# Feuille1.net
KiCad netlist of a schematic drawn in Altium Designer
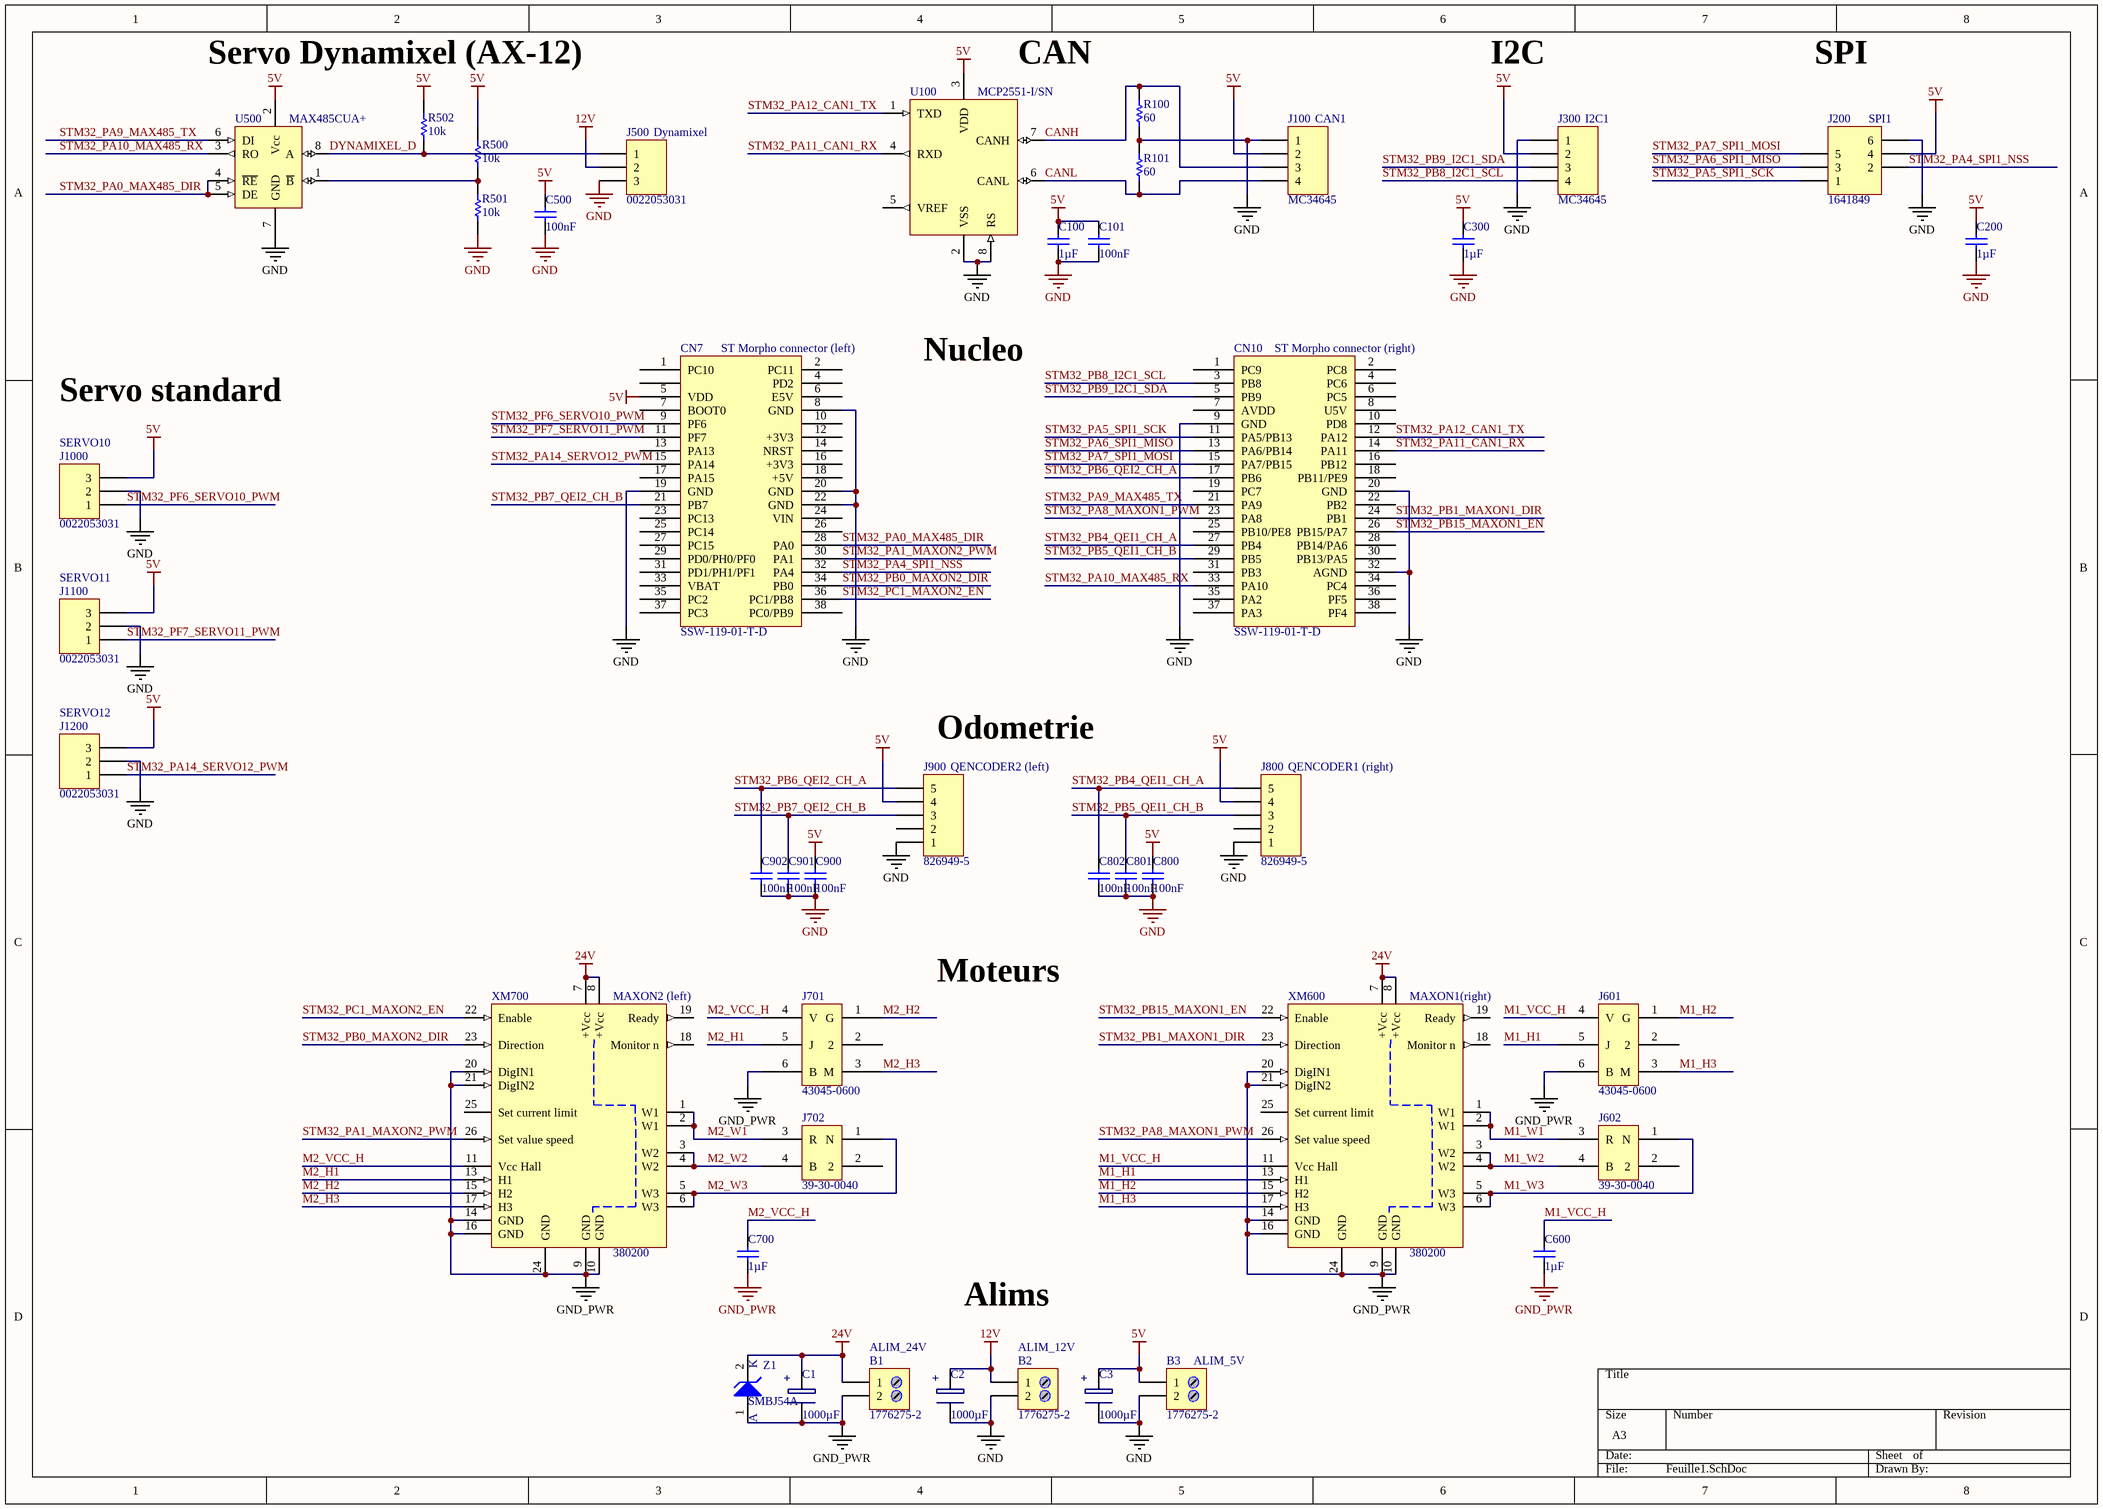
[diagram p0: Feuille1.SchDoc]

(export (version "E")
  (design (tool "Eeschema 10.0.6"))
  (components
    (comp (ref "B1")
      (value "1776275-2")
      (footprint "BORNIER_2V_3.5MM")
      (description "TERM BLOCK 2POS SIDE ENT 3.5MM")
      (fields (field (name "MANUFACTURER") "TE Connectivity AMP Connectors"))
      (libsource (lib "Divers") (part "1776275-2"))
    )
    (comp (ref "B2")
      (value "1776275-2")
      (footprint "BORNIER_2V_3.5MM")
      (description "TERM BLOCK 2POS SIDE ENT 3.5MM")
      (fields (field (name "MANUFACTURER") "TE Connectivity AMP Connectors"))
      (libsource (lib "Divers") (part "1776275-2"))
    )
    (comp (ref "B3")
      (value "1776275-2")
      (footprint "BORNIER_2V_3.5MM")
      (description "TERM BLOCK 2POS SIDE ENT 3.5MM")
      (fields (field (name "MANUFACTURER") "TE Connectivity AMP Connectors"))
      (libsource (lib "Divers") (part "1776275-2"))
    )
    (comp (ref "C1")
      (value "1000µF")
      (footprint "C_10mm")
      (fields
        (field (name "MANUFACTURER") "PANASONIC")
        (field (name "MANUFACTURER PART NUMBER") "EEUHD1E102")
      )
      (libsource (lib "Capas_Chimiques") (part "C_1000µF"))
    )
    (comp (ref "C2")
      (value "1000µF")
      (footprint "C_10mm")
      (fields
        (field (name "MANUFACTURER") "PANASONIC")
        (field (name "MANUFACTURER PART NUMBER") "EEUHD1E102")
      )
      (libsource (lib "Capas_Chimiques") (part "C_1000µF"))
    )
    (comp (ref "C3")
      (value "1000µF")
      (footprint "C_10mm")
      (fields
        (field (name "MANUFACTURER") "PANASONIC")
        (field (name "MANUFACTURER PART NUMBER") "EEUHD1E102")
      )
      (libsource (lib "Capas_Chimiques") (part "C_1000µF"))
    )
    (comp (ref "C100")
      (value "1µF")
      (footprint "C0805_N")
      (description "Capacitor")
      (fields (field (name "PUBLISHER") "Altium Limited"))
      (libsource (lib "_ROBOT") (part "Condensateur"))
    )
    (comp (ref "C101")
      (value "100nF")
      (footprint "C0805_N")
      (description "Capacitor")
      (fields (field (name "PUBLISHER") "Altium Limited"))
      (libsource (lib "_ROBOT") (part "Condensateur"))
    )
    (comp (ref "C200")
      (value "1µF")
      (footprint "C0805_N")
      (description "Capacitor")
      (fields (field (name "PUBLISHER") "Altium Limited"))
      (libsource (lib "_ROBOT") (part "Condensateur"))
    )
    (comp (ref "C300")
      (value "1µF")
      (footprint "C0805_N")
      (description "Capacitor")
      (fields (field (name "PUBLISHER") "Altium Limited"))
      (libsource (lib "_ROBOT") (part "Condensateur"))
    )
    (comp (ref "C500")
      (value "100nF")
      (footprint "C0805_N")
      (description "Capacitor")
      (fields (field (name "PUBLISHER") "Altium Limited"))
      (libsource (lib "_ROBOT") (part "Condensateur"))
    )
    (comp (ref "C600")
      (value "1µF")
      (footprint "C0805_N")
      (description "Capacitor")
      (fields (field (name "PUBLISHER") "Altium Limited"))
      (libsource (lib "_ROBOT") (part "Condensateur"))
    )
    (comp (ref "C700")
      (value "1µF")
      (footprint "C0805_N")
      (description "Capacitor")
      (fields (field (name "PUBLISHER") "Altium Limited"))
      (libsource (lib "_ROBOT") (part "Condensateur"))
    )
    (comp (ref "C800")
      (value "100nF")
      (footprint "C0805_N")
      (description "Capacitor")
      (fields (field (name "PUBLISHER") "Altium Limited"))
      (libsource (lib "_ROBOT") (part "Condensateur"))
    )
    (comp (ref "C801")
      (value "100nF")
      (footprint "C0805_N")
      (description "Capacitor")
      (fields (field (name "PUBLISHER") "Altium Limited"))
      (libsource (lib "_ROBOT") (part "Condensateur"))
    )
    (comp (ref "C802")
      (value "100nF")
      (footprint "C0805_N")
      (description "Capacitor")
      (fields (field (name "PUBLISHER") "Altium Limited"))
      (libsource (lib "_ROBOT") (part "Condensateur"))
    )
    (comp (ref "C900")
      (value "100nF")
      (footprint "C0805_N")
      (description "Capacitor")
      (fields (field (name "PUBLISHER") "Altium Limited"))
      (libsource (lib "_ROBOT") (part "Condensateur"))
    )
    (comp (ref "C901")
      (value "100nF")
      (footprint "C0805_N")
      (description "Capacitor")
      (fields (field (name "PUBLISHER") "Altium Limited"))
      (libsource (lib "_ROBOT") (part "Condensateur"))
    )
    (comp (ref "C902")
      (value "100nF")
      (footprint "C0805_N")
      (description "Capacitor")
      (fields (field (name "PUBLISHER") "Altium Limited"))
      (libsource (lib "_ROBOT") (part "Condensateur"))
    )
    (comp (ref "CN7")
      (value "SSW-119-01-T-D")
      (footprint "Samtec:CONN RCPT .100\" 38POS DUAL TIN")
      (description "CONN RCPT .100\" 38POS DUAL TIN")
      (fields (field (name "MANUFACTURER") "Samtec Inc."))
      (libsource (lib "Samtec") (part "SSW-119-01-T-D"))
    )
    (comp (ref "CN10")
      (value "SSW-119-01-T-D")
      (footprint "Samtec:CONN RCPT .100\" 38POS DUAL TIN")
      (description "CONN RCPT .100\" 38POS DUAL TIN")
      (fields (field (name "MANUFACTURER") "Samtec Inc."))
      (libsource (lib "Samtec") (part "SSW-119-01-T-D"))
    )
    (comp (ref "J100")
      (value "MC34645")
      (footprint "HDR1X4")
      (description "MULTICOMP - MC34645 - EMB. MALE COUDEE  CON. MALE 2.54MM 4VOIE")
      (fields (field (name "MANUFACTURER") "MULTICOMP"))
      (libsource (lib "Divers") (part "MC34645"))
    )
    (comp (ref "J200")
      (value "~")
      (footprint "Wurth:690367280676")
      (description "WR-MM Female SMT Connector with Polarization")
      (fields
        (field (name "MANUFACTURER PART NUMBER") "690367280676")
        (field (name "SUPPLIER PART NUMBER 1") "1641849")
      )
      (libsource (lib "Connecteurs") (part "WE-WR-MM Female SMT Connector with Polarization 690367280676"))
    )
    (comp (ref "J300")
      (value "MC34645")
      (footprint "HDR1X4")
      (description "MULTICOMP - MC34645 - EMB. MALE COUDEE  CON. MALE 2.54MM 4VOIE")
      (fields (field (name "MANUFACTURER") "MULTICOMP"))
      (libsource (lib "Divers") (part "MC34645"))
    )
    (comp (ref "J500")
      (value "0022053031")
      (footprint "HDR1X3")
      (description "CONN HEADER 3POS .100 R/A TIN")
      (fields (field (name "MANUFACTURER") "Molex, LLC"))
      (libsource (lib "Divers") (part "0022053031"))
    )
    (comp (ref "J601")
      (value "43045-0600")
      (footprint "Molex:43045-0600")
      (description "CONN HEADER 6POS 3MM RT ANG TIN")
      (fields (field (name "MANUFACTURER") "MOLEX"))
      (libsource (lib "Connecteurs") (part "43045-0600"))
    )
    (comp (ref "J602")
      (value "39-30-0040")
      (footprint "Molex:39-30-0040")
      (description "MOLEX  39-30-0040 4.2 mm, 4 Contact(s)")
      (fields (field (name "MANUFACTURER") "MOLEX"))
      (libsource (lib "Connecteurs") (part "39-30-0040"))
    )
    (comp (ref "J701")
      (value "43045-0600")
      (footprint "Molex:43045-0600")
      (description "CONN HEADER 6POS 3MM RT ANG TIN")
      (fields (field (name "MANUFACTURER") "MOLEX"))
      (libsource (lib "Connecteurs") (part "43045-0600"))
    )
    (comp (ref "J702")
      (value "39-30-0040")
      (footprint "Molex:39-30-0040")
      (description "MOLEX  39-30-0040 4.2 mm, 4 Contact(s)")
      (fields (field (name "MANUFACTURER") "MOLEX"))
      (libsource (lib "Connecteurs") (part "39-30-0040"))
    )
    (comp (ref "J800")
      (value "826949-5")
      (footprint "HDR1X5")
      (description "CONN HEADER BRKWY 5POS R/A TIN")
      (fields (field (name "MANUFACTURER") "TE Connectivity AMP Connectors"))
      (libsource (lib "Divers") (part "826949-5"))
    )
    (comp (ref "J900")
      (value "826949-5")
      (footprint "HDR1X5")
      (description "CONN HEADER BRKWY 5POS R/A TIN")
      (fields (field (name "MANUFACTURER") "TE Connectivity AMP Connectors"))
      (libsource (lib "Divers") (part "826949-5"))
    )
    (comp (ref "J1000")
      (value "0022053031")
      (footprint "HDR1X3")
      (description "CONN HEADER 3POS .100 R/A TIN")
      (fields (field (name "MANUFACTURER") "Molex, LLC"))
      (libsource (lib "") (part "0022053031_1"))
    )
    (comp (ref "J1100")
      (value "0022053031")
      (footprint "HDR1X3")
      (description "CONN HEADER 3POS .100 R/A TIN")
      (fields (field (name "MANUFACTURER") "Molex, LLC"))
      (libsource (lib "") (part "0022053031_1"))
    )
    (comp (ref "J1200")
      (value "0022053031")
      (footprint "HDR1X3")
      (description "CONN HEADER 3POS .100 R/A TIN")
      (fields (field (name "MANUFACTURER") "Molex, LLC"))
      (libsource (lib "") (part "0022053031_1"))
    )
    (comp (ref "R100")
      (value "60")
      (footprint "R0805_N")
      (description "Resistor")
      (fields (field (name "PUBLISHER") "Altium Limited"))
      (libsource (lib "_ROBOT") (part "Resistor"))
    )
    (comp (ref "R101")
      (value "60")
      (footprint "R0805_N")
      (description "Resistor")
      (fields (field (name "PUBLISHER") "Altium Limited"))
      (libsource (lib "_ROBOT") (part "Resistor"))
    )
    (comp (ref "R500")
      (value "10k")
      (footprint "R0805_N")
      (description "Resistor")
      (fields (field (name "PUBLISHER") "Altium Limited"))
      (libsource (lib "_ROBOT") (part "Resistor"))
    )
    (comp (ref "R501")
      (value "10k")
      (footprint "R0805_N")
      (description "Resistor")
      (fields (field (name "PUBLISHER") "Altium Limited"))
      (libsource (lib "_ROBOT") (part "Resistor"))
    )
    (comp (ref "R502")
      (value "10k")
      (footprint "R0805_N")
      (description "Resistor")
      (fields (field (name "PUBLISHER") "Altium Limited"))
      (libsource (lib "_ROBOT") (part "Resistor"))
    )
    (comp (ref "U100")
      (value "MCP2551-I/SN")
      (footprint "SO8_N")
      (description "IC TRANSCEIVER CAN HI-SPD 8-SOIC")
      (fields (field (name "MANUFACTURER") "Microchip Technology"))
      (libsource (lib "Serial") (part "MCP2551-I/SN"))
    )
    (comp (ref "U500")
      (value "MAX485CUA+")
      (footprint "Serial_goldo:MMAX-8")
      (description "IC TXRX RS485/RS422 8-UMAX")
      (fields (field (name "MANUFACTURER") "Maxim Integrated"))
      (libsource (lib "Serial") (part "MAX485CUA+"))
    )
    (comp (ref "XM600")
      (value "380200")
      (footprint "Divers_goldo:380200_goldo")
      (description "DEC Module 50/5, amplificateur EC 1 Q 50 V / 5 A, régulation de vitesse, module OEM")
      (fields (field (name "MANUFACTURER") "Maxon Motor"))
      (libsource (lib "Divers") (part "380200"))
    )
    (comp (ref "XM700")
      (value "380200")
      (footprint "Divers_goldo:380200_goldo")
      (description "DEC Module 50/5, amplificateur EC 1 Q 50 V / 5 A, régulation de vitesse, module OEM")
      (fields (field (name "MANUFACTURER") "Maxon Motor"))
      (libsource (lib "Divers") (part "380200"))
    )
    (comp (ref "Z1")
      (value "SMBJ54A")
      (footprint "Redressement_goldo:SMA Diode (DO-214AA)")
      (description "DIODE TVS (Transil unidirectionelle)")
      (fields (field (name "MANUFACTURER") "ON Semiconductor"))
      (libsource (lib "Redressement_goldo") (part "SMBJ54A"))
    )
  )
  (nets
    (net (code "1") (name "/CANH") (class "Default")
      (node (ref "J100") (pin "3") (pinfunction "3_3") (pintype "passive"))
      (node (ref "R100") (pin "2") (pinfunction "2_2") (pintype "passive"))
      (node (ref "U100") (pin "7") (pinfunction "CANH_7") (pintype "bidirectional"))
    )
    (net (code "2") (name "/CANL") (class "Default")
      (node (ref "J100") (pin "4") (pinfunction "4_4") (pintype "passive"))
      (node (ref "R101") (pin "1") (pinfunction "1_1") (pintype "passive"))
      (node (ref "U100") (pin "6") (pinfunction "CANL_6") (pintype "bidirectional"))
    )
    (net (code "3") (name "/DYNAMIXEL_D") (class "Default")
      (node (ref "J500") (pin "1") (pinfunction "1_1") (pintype "passive"))
      (node (ref "R502") (pin "1") (pinfunction "1_1") (pintype "passive"))
      (node (ref "U500") (pin "8") (pinfunction "A_8") (pintype "bidirectional"))
    )
    (net (code "4") (name "/M1_H1") (class "Default")
      (node (ref "J601") (pin "5") (pinfunction "J_5") (pintype "passive"))
      (node (ref "XM600") (pin "13") (pinfunction "H1_13") (pintype "input"))
    )
    (net (code "5") (name "/M1_H2") (class "Default")
      (node (ref "J601") (pin "1") (pinfunction "G_1") (pintype "passive"))
      (node (ref "XM600") (pin "15") (pinfunction "H2_15") (pintype "input"))
    )
    (net (code "6") (name "/M1_H3") (class "Default")
      (node (ref "J601") (pin "3") (pinfunction "M_3") (pintype "passive"))
      (node (ref "XM600") (pin "17") (pinfunction "H3_17") (pintype "input"))
    )
    (net (code "7") (name "/M1_VCC_H") (class "Default")
      (node (ref "C600") (pin "2") (pinfunction "2_2") (pintype "passive"))
      (node (ref "J601") (pin "4") (pinfunction "V_4") (pintype "passive"))
      (node (ref "XM600") (pin "11") (pinfunction "Vcc_Hall_11") (pintype "power_in"))
    )
    (net (code "8") (name "/M1_W1") (class "Default")
      (node (ref "J602") (pin "3") (pinfunction "R_3") (pintype "passive"))
      (node (ref "XM600") (pin "1") (pinfunction "W1_1") (pintype "passive"))
      (node (ref "XM600") (pin "2") (pinfunction "W1_2") (pintype "passive"))
    )
    (net (code "9") (name "/M1_W2") (class "Default")
      (node (ref "J602") (pin "4") (pinfunction "B_4") (pintype "passive"))
      (node (ref "XM600") (pin "3") (pinfunction "W2_3") (pintype "passive"))
      (node (ref "XM600") (pin "4") (pinfunction "W2_4") (pintype "passive"))
    )
    (net (code "10") (name "/M1_W3") (class "Default")
      (node (ref "J602") (pin "1") (pinfunction "N_1") (pintype "passive"))
      (node (ref "XM600") (pin "5") (pinfunction "W3_5") (pintype "passive"))
      (node (ref "XM600") (pin "6") (pinfunction "W3_6") (pintype "passive"))
    )
    (net (code "11") (name "/M2_H1") (class "Default")
      (node (ref "J701") (pin "5") (pinfunction "J_5") (pintype "passive"))
      (node (ref "XM700") (pin "13") (pinfunction "H1_13") (pintype "input"))
    )
    (net (code "12") (name "/M2_H2") (class "Default")
      (node (ref "J701") (pin "1") (pinfunction "G_1") (pintype "passive"))
      (node (ref "XM700") (pin "15") (pinfunction "H2_15") (pintype "input"))
    )
    (net (code "13") (name "/M2_H3") (class "Default")
      (node (ref "J701") (pin "3") (pinfunction "M_3") (pintype "passive"))
      (node (ref "XM700") (pin "17") (pinfunction "H3_17") (pintype "input"))
    )
    (net (code "14") (name "/M2_VCC_H") (class "Default")
      (node (ref "C700") (pin "2") (pinfunction "2_2") (pintype "passive"))
      (node (ref "J701") (pin "4") (pinfunction "V_4") (pintype "passive"))
      (node (ref "XM700") (pin "11") (pinfunction "Vcc_Hall_11") (pintype "power_in"))
    )
    (net (code "15") (name "/M2_W1") (class "Default")
      (node (ref "J702") (pin "3") (pinfunction "R_3") (pintype "passive"))
      (node (ref "XM700") (pin "1") (pinfunction "W1_1") (pintype "passive"))
      (node (ref "XM700") (pin "2") (pinfunction "W1_2") (pintype "passive"))
    )
    (net (code "16") (name "/M2_W2") (class "Default")
      (node (ref "J702") (pin "4") (pinfunction "B_4") (pintype "passive"))
      (node (ref "XM700") (pin "3") (pinfunction "W2_3") (pintype "passive"))
      (node (ref "XM700") (pin "4") (pinfunction "W2_4") (pintype "passive"))
    )
    (net (code "17") (name "/M2_W3") (class "Default")
      (node (ref "J702") (pin "1") (pinfunction "N_1") (pintype "passive"))
      (node (ref "XM700") (pin "5") (pinfunction "W3_5") (pintype "passive"))
      (node (ref "XM700") (pin "6") (pinfunction "W3_6") (pintype "passive"))
    )
    (net (code "18") (name "/STM32_PA0_MAX485_DIR") (class "Default")
      (node (ref "CN7") (pin "28") (pinfunction "PA0_28") (pintype "passive"))
      (node (ref "U500") (pin "4") (pinfunction "~{RE}_4") (pintype "input"))
      (node (ref "U500") (pin "5") (pinfunction "DE_5") (pintype "input"))
    )
    (net (code "19") (name "/STM32_PA1_MAXON2_PWM") (class "Default")
      (node (ref "CN7") (pin "30") (pinfunction "PA1_30") (pintype "passive"))
      (node (ref "XM700") (pin "26") (pinfunction "Set_value_speed_26") (pintype "input"))
    )
    (net (code "20") (name "/STM32_PA4_SPI1_NSS") (class "Default")
      (node (ref "CN7") (pin "32") (pinfunction "PA4_32") (pintype "passive"))
      (node (ref "J200") (pin "2") (pinfunction "2_2") (pintype "passive"))
    )
    (net (code "21") (name "/STM32_PA5_SPI1_SCK") (class "Default")
      (node (ref "CN10") (pin "11") (pinfunction "PF7_11") (pintype "passive"))
      (node (ref "J200") (pin "1") (pinfunction "1_1") (pintype "passive"))
    )
    (net (code "22") (name "/STM32_PA6_SPI1_MISO") (class "Default")
      (node (ref "CN10") (pin "13") (pinfunction "PA13_13") (pintype "passive"))
      (node (ref "J200") (pin "3") (pinfunction "3_3") (pintype "passive"))
    )
    (net (code "23") (name "/STM32_PA7_SPI1_MOSI") (class "Default")
      (node (ref "CN10") (pin "15") (pinfunction "PA14_15") (pintype "passive"))
      (node (ref "J200") (pin "5") (pinfunction "5_5") (pintype "passive"))
    )
    (net (code "24") (name "/STM32_PA8_MAXON1_PWM") (class "Default")
      (node (ref "CN10") (pin "23") (pinfunction "PC13_23") (pintype "passive"))
      (node (ref "XM600") (pin "26") (pinfunction "Set_value_speed_26") (pintype "input"))
    )
    (net (code "25") (name "/STM32_PA9_MAX485_TX") (class "Default")
      (node (ref "CN10") (pin "21") (pinfunction "PB7_21") (pintype "passive"))
      (node (ref "U500") (pin "6") (pinfunction "DI_6") (pintype "input"))
    )
    (net (code "26") (name "/STM32_PA10_MAX485_RX") (class "Default")
      (node (ref "CN10") (pin "33") (pinfunction "VBAT_33") (pintype "passive"))
      (node (ref "U500") (pin "3") (pinfunction "RO_3") (pintype "output"))
    )
    (net (code "27") (name "/STM32_PA11_CAN1_RX") (class "Default")
      (node (ref "CN10") (pin "14") (pinfunction "NRST_14") (pintype "passive"))
      (node (ref "U100") (pin "4") (pinfunction "RXD_4") (pintype "output"))
    )
    (net (code "28") (name "/STM32_PA12_CAN1_TX") (class "Default")
      (node (ref "CN10") (pin "12") (pinfunction "+3V3_12") (pintype "passive"))
      (node (ref "U100") (pin "1") (pinfunction "TXD_1") (pintype "input"))
    )
    (net (code "29") (name "/STM32_PA14_SERVO12_PWM") (class "Default")
      (node (ref "CN7") (pin "15") (pinfunction "PA14_15") (pintype "passive"))
      (node (ref "J1200") (pin "1") (pinfunction "1_1") (pintype "passive"))
    )
    (net (code "30") (name "/STM32_PB0_MAXON2_DIR") (class "Default")
      (node (ref "CN7") (pin "34") (pinfunction "PB0_34") (pintype "passive"))
      (node (ref "XM700") (pin "23") (pinfunction "Direction_23") (pintype "input"))
    )
    (net (code "31") (name "/STM32_PB1_MAXON1_DIR") (class "Default")
      (node (ref "CN10") (pin "24") (pinfunction "VIN_24") (pintype "passive"))
      (node (ref "XM600") (pin "23") (pinfunction "Direction_23") (pintype "input"))
    )
    (net (code "32") (name "/STM32_PB4_QEI1_CH_A") (class "Default")
      (node (ref "C802") (pin "2") (pinfunction "2_2") (pintype "passive"))
      (node (ref "CN10") (pin "27") (pinfunction "PC15_27") (pintype "passive"))
      (node (ref "J800") (pin "5") (pinfunction "5_5") (pintype "passive"))
    )
    (net (code "33") (name "/STM32_PB5_QEI1_CH_B") (class "Default")
      (node (ref "C801") (pin "2") (pinfunction "2_2") (pintype "passive"))
      (node (ref "CN10") (pin "29") (pinfunction "PD0/PH0/PF0_29") (pintype "passive"))
      (node (ref "J800") (pin "3") (pinfunction "3_3") (pintype "passive"))
    )
    (net (code "34") (name "/STM32_PB6_QEI2_CH_A") (class "Default")
      (node (ref "C902") (pin "2") (pinfunction "2_2") (pintype "passive"))
      (node (ref "CN10") (pin "17") (pinfunction "PA15_17") (pintype "passive"))
      (node (ref "J900") (pin "5") (pinfunction "5_5") (pintype "passive"))
    )
    (net (code "35") (name "/STM32_PB7_QEI2_CH_B") (class "Default")
      (node (ref "C901") (pin "2") (pinfunction "2_2") (pintype "passive"))
      (node (ref "CN7") (pin "21") (pinfunction "PB7_21") (pintype "passive"))
      (node (ref "J900") (pin "3") (pinfunction "3_3") (pintype "passive"))
    )
    (net (code "36") (name "/STM32_PB8_I2C1_SCL") (class "Default")
      (node (ref "CN10") (pin "3") (pinfunction "PC12_3") (pintype "passive"))
      (node (ref "J300") (pin "4") (pinfunction "4_4") (pintype "passive"))
    )
    (net (code "37") (name "/STM32_PB9_I2C1_SDA") (class "Default")
      (node (ref "CN10") (pin "5") (pinfunction "VDD_5") (pintype "passive"))
      (node (ref "J300") (pin "3") (pinfunction "3_3") (pintype "passive"))
    )
    (net (code "38") (name "/STM32_PB15_MAXON1_EN") (class "Default")
      (node (ref "CN10") (pin "26") (pintype "passive"))
      (node (ref "XM600") (pin "22") (pinfunction "Enable_22") (pintype "input"))
    )
    (net (code "39") (name "/STM32_PC1_MAXON2_EN") (class "Default")
      (node (ref "CN7") (pin "36") (pinfunction "PC1/PB8_36") (pintype "passive"))
      (node (ref "XM700") (pin "22") (pinfunction "Enable_22") (pintype "input"))
    )
    (net (code "40") (name "/STM32_PF6_SERVO10_PWM") (class "Default")
      (node (ref "CN7") (pin "9") (pinfunction "PF6_9") (pintype "passive"))
      (node (ref "J1000") (pin "1") (pinfunction "1_1") (pintype "passive"))
    )
    (net (code "41") (name "/STM32_PF7_SERVO11_PWM") (class "Default")
      (node (ref "CN7") (pin "11") (pinfunction "PF7_11") (pintype "passive"))
      (node (ref "J1100") (pin "1") (pinfunction "1_1") (pintype "passive"))
    )
    (net (code "42") (name "5V") (class "Default")
      (node (ref "B3") (pin "1") (pinfunction "1_1") (pintype "passive"))
      (node (ref "C100") (pin "2") (pinfunction "2_2") (pintype "passive"))
      (node (ref "C101") (pin "2") (pinfunction "2_2") (pintype "passive"))
      (node (ref "C200") (pin "2") (pinfunction "2_2") (pintype "passive"))
      (node (ref "C3") (pin "2") (pinfunction "2_2") (pintype "passive"))
      (node (ref "C300") (pin "2") (pinfunction "2_2") (pintype "passive"))
      (node (ref "C500") (pin "2") (pinfunction "2_2") (pintype "passive"))
      (node (ref "C800") (pin "2") (pinfunction "2_2") (pintype "passive"))
      (node (ref "C900") (pin "2") (pinfunction "2_2") (pintype "passive"))
      (node (ref "CN7") (pin "5") (pinfunction "VDD_5") (pintype "passive"))
      (node (ref "J100") (pin "2") (pinfunction "2_2") (pintype "passive"))
      (node (ref "J1000") (pin "3") (pinfunction "3_3") (pintype "passive"))
      (node (ref "J1100") (pin "3") (pinfunction "3_3") (pintype "passive"))
      (node (ref "J1200") (pin "3") (pinfunction "3_3") (pintype "passive"))
      (node (ref "J200") (pin "4") (pinfunction "4_4") (pintype "passive"))
      (node (ref "J300") (pin "2") (pinfunction "2_2") (pintype "passive"))
      (node (ref "J800") (pin "4") (pinfunction "4_4") (pintype "passive"))
      (node (ref "J900") (pin "4") (pinfunction "4_4") (pintype "passive"))
      (node (ref "R500") (pin "2") (pinfunction "2_2") (pintype "passive"))
      (node (ref "R502") (pin "2") (pinfunction "2_2") (pintype "passive"))
      (node (ref "U100") (pin "3") (pinfunction "VDD_3") (pintype "power_in"))
      (node (ref "U500") (pin "2") (pinfunction "Vcc_2") (pintype "power_in"))
    )
    (net (code "43") (name "12V") (class "Default")
      (node (ref "B2") (pin "1") (pinfunction "1_1") (pintype "passive"))
      (node (ref "C2") (pin "2") (pinfunction "2_2") (pintype "passive"))
      (node (ref "J500") (pin "2") (pinfunction "2_2") (pintype "passive"))
    )
    (net (code "44") (name "24V") (class "Default")
      (node (ref "B1") (pin "1") (pinfunction "1_1") (pintype "passive"))
      (node (ref "C1") (pin "2") (pinfunction "2_2") (pintype "passive"))
      (node (ref "XM600") (pin "7") (pinfunction "+Vcc_7") (pintype "power_in"))
      (node (ref "XM600") (pin "8") (pinfunction "+Vcc_8") (pintype "power_in"))
      (node (ref "XM700") (pin "7") (pinfunction "+Vcc_7") (pintype "power_in"))
      (node (ref "XM700") (pin "8") (pinfunction "+Vcc_8") (pintype "power_in"))
      (node (ref "Z1") (pin "2") (pintype "passive"))
    )
    (net (code "45") (name "GND") (class "Default")
      (node (ref "B2") (pin "2") (pinfunction "2_2") (pintype "passive"))
      (node (ref "B3") (pin "2") (pinfunction "2_2") (pintype "passive"))
      (node (ref "C100") (pin "1") (pinfunction "1_1") (pintype "passive"))
      (node (ref "C101") (pin "1") (pinfunction "1_1") (pintype "passive"))
      (node (ref "C2") (pin "1") (pinfunction "1_1") (pintype "passive"))
      (node (ref "C200") (pin "1") (pinfunction "1_1") (pintype "passive"))
      (node (ref "C3") (pin "1") (pinfunction "1_1") (pintype "passive"))
      (node (ref "C300") (pin "1") (pinfunction "1_1") (pintype "passive"))
      (node (ref "C500") (pin "1") (pinfunction "1_1") (pintype "passive"))
      (node (ref "C800") (pin "1") (pinfunction "1_1") (pintype "passive"))
      (node (ref "C801") (pin "1") (pinfunction "1_1") (pintype "passive"))
      (node (ref "C802") (pin "1") (pinfunction "1_1") (pintype "passive"))
      (node (ref "C900") (pin "1") (pinfunction "1_1") (pintype "passive"))
      (node (ref "C901") (pin "1") (pinfunction "1_1") (pintype "passive"))
      (node (ref "C902") (pin "1") (pinfunction "1_1") (pintype "passive"))
      (node (ref "CN10") (pin "20") (pinfunction "GND_20") (pintype "passive"))
      (node (ref "CN10") (pin "32") (pinfunction "PA4_32") (pintype "passive"))
      (node (ref "CN10") (pin "9") (pinfunction "PF6_9") (pintype "passive"))
      (node (ref "CN7") (pin "19") (pinfunction "GND_19") (pintype "passive"))
      (node (ref "CN7") (pin "20") (pinfunction "GND_20") (pintype "passive"))
      (node (ref "CN7") (pin "22") (pinfunction "GND_22") (pintype "passive"))
      (node (ref "CN7") (pin "8") (pinfunction "GND_8") (pintype "passive"))
      (node (ref "J100") (pin "1") (pinfunction "1_1") (pintype "passive"))
      (node (ref "J1000") (pin "2") (pinfunction "2_2") (pintype "passive"))
      (node (ref "J1100") (pin "2") (pinfunction "2_2") (pintype "passive"))
      (node (ref "J1200") (pin "2") (pinfunction "2_2") (pintype "passive"))
      (node (ref "J200") (pin "6") (pinfunction "6_6") (pintype "passive"))
      (node (ref "J300") (pin "1") (pinfunction "1_1") (pintype "passive"))
      (node (ref "J500") (pin "3") (pinfunction "3_3") (pintype "passive"))
      (node (ref "J800") (pin "1") (pinfunction "1_1") (pintype "passive"))
      (node (ref "J900") (pin "1") (pinfunction "1_1") (pintype "passive"))
      (node (ref "R100") (pin "1") (pinfunction "1_1") (pintype "passive"))
      (node (ref "R101") (pin "2") (pinfunction "2_2") (pintype "passive"))
      (node (ref "R501") (pin "1") (pinfunction "1_1") (pintype "passive"))
      (node (ref "U100") (pin "2") (pinfunction "VSS_2") (pintype "power_in"))
      (node (ref "U100") (pin "8") (pinfunction "RS_8") (pintype "input"))
      (node (ref "U500") (pin "7") (pinfunction "GND_7") (pintype "power_in"))
    )
    (net (code "46") (name "GND_PWR") (class "Default")
      (node (ref "B1") (pin "2") (pinfunction "2_2") (pintype "passive"))
      (node (ref "C1") (pin "1") (pinfunction "1_1") (pintype "passive"))
      (node (ref "C600") (pin "1") (pinfunction "1_1") (pintype "passive"))
      (node (ref "C700") (pin "1") (pinfunction "1_1") (pintype "passive"))
      (node (ref "J601") (pin "6") (pinfunction "B_6") (pintype "passive"))
      (node (ref "J701") (pin "6") (pinfunction "B_6") (pintype "passive"))
      (node (ref "XM600") (pin "10") (pinfunction "GND_10") (pintype "power_in"))
      (node (ref "XM600") (pin "14") (pinfunction "GND_14") (pintype "power_in"))
      (node (ref "XM600") (pin "16") (pinfunction "GND_16") (pintype "power_in"))
      (node (ref "XM600") (pin "20") (pinfunction "DigIN1_20") (pintype "input"))
      (node (ref "XM600") (pin "21") (pinfunction "DigIN2_21") (pintype "input"))
      (node (ref "XM600") (pin "24") (pinfunction "GND_24") (pintype "power_in"))
      (node (ref "XM600") (pin "9") (pinfunction "GND_9") (pintype "power_in"))
      (node (ref "XM700") (pin "10") (pinfunction "GND_10") (pintype "power_in"))
      (node (ref "XM700") (pin "14") (pinfunction "GND_14") (pintype "power_in"))
      (node (ref "XM700") (pin "16") (pinfunction "GND_16") (pintype "power_in"))
      (node (ref "XM700") (pin "20") (pinfunction "DigIN1_20") (pintype "input"))
      (node (ref "XM700") (pin "21") (pinfunction "DigIN2_21") (pintype "input"))
      (node (ref "XM700") (pin "24") (pinfunction "GND_24") (pintype "power_in"))
      (node (ref "XM700") (pin "9") (pinfunction "GND_9") (pintype "power_in"))
      (node (ref "Z1") (pin "1") (pintype "passive"))
    )
    (net (code "47") (name "Net-(U500-~{B})") (class "Default")
      (node (ref "R500") (pin "1") (pinfunction "1_1") (pintype "passive"))
      (node (ref "R501") (pin "2") (pinfunction "2_2") (pintype "passive"))
      (node (ref "U500") (pin "1") (pinfunction "~{B}_1") (pintype "bidirectional"))
    )
    (net (code "48") (name "unconnected-(CN7-+3V3-Pad12)") (class "Default")
      (node (ref "CN7") (pin "12") (pinfunction "+3V3_12") (pintype "passive"))
    )
    (net (code "49") (name "unconnected-(CN7-+3V3-Pad16)") (class "Default")
      (node (ref "CN7") (pin "16") (pinfunction "+3V3_16") (pintype "passive"))
    )
    (net (code "50") (name "unconnected-(CN7-+5V-Pad18)") (class "Default")
      (node (ref "CN7") (pin "18") (pinfunction "+5V_18") (pintype "passive"))
    )
    (net (code "51") (name "unconnected-(CN7-BOOT0-Pad7)") (class "Default")
      (node (ref "CN7") (pin "7") (pinfunction "BOOT0_7") (pintype "passive"))
    )
    (net (code "52") (name "unconnected-(CN7-E5V-Pad6)") (class "Default")
      (node (ref "CN7") (pin "6") (pinfunction "E5V_6") (pintype "passive"))
    )
    (net (code "53") (name "unconnected-(CN7-NRST-Pad14)") (class "Default")
      (node (ref "CN7") (pin "14") (pinfunction "NRST_14") (pintype "passive"))
    )
    (net (code "54") (name "unconnected-(CN7-PA13-Pad13)") (class "Default")
      (node (ref "CN7") (pin "13") (pinfunction "PA13_13") (pintype "passive"))
    )
    (net (code "55") (name "unconnected-(CN7-PA15-Pad17)") (class "Default")
      (node (ref "CN7") (pin "17") (pinfunction "PA15_17") (pintype "passive"))
    )
    (net (code "56") (name "unconnected-(CN7-PC0{slash}PB9-Pad38)") (class "Default")
      (node (ref "CN7") (pin "38") (pinfunction "PC0/PB9_38") (pintype "passive"))
    )
    (net (code "57") (name "unconnected-(CN7-PC2-Pad35)") (class "Default")
      (node (ref "CN7") (pin "35") (pinfunction "PC2_35") (pintype "passive"))
    )
    (net (code "58") (name "unconnected-(CN7-PC3-Pad37)") (class "Default")
      (node (ref "CN7") (pin "37") (pinfunction "PC3_37") (pintype "passive"))
    )
    (net (code "59") (name "unconnected-(CN7-PC10-Pad1)") (class "Default")
      (node (ref "CN7") (pin "1") (pinfunction "PC10_1") (pintype "passive"))
    )
    (net (code "60") (name "unconnected-(CN7-PC11-Pad2)") (class "Default")
      (node (ref "CN7") (pin "2") (pinfunction "PC11_2") (pintype "passive"))
    )
    (net (code "61") (name "unconnected-(CN7-PC12-Pad3)") (class "Default")
      (node (ref "CN7") (pin "3") (pinfunction "PC12_3") (pintype "passive"))
    )
    (net (code "62") (name "unconnected-(CN7-PC13-Pad23)") (class "Default")
      (node (ref "CN7") (pin "23") (pinfunction "PC13_23") (pintype "passive"))
    )
    (net (code "63") (name "unconnected-(CN7-PC14-Pad25)") (class "Default")
      (node (ref "CN7") (pin "25") (pinfunction "PC14_25") (pintype "passive"))
    )
    (net (code "64") (name "unconnected-(CN7-PC15-Pad27)") (class "Default")
      (node (ref "CN7") (pin "27") (pinfunction "PC15_27") (pintype "passive"))
    )
    (net (code "65") (name "unconnected-(CN7-PD0{slash}PH0{slash}PF0-Pad29)") (class "Default")
      (node (ref "CN7") (pin "29") (pinfunction "PD0/PH0/PF0_29") (pintype "passive"))
    )
    (net (code "66") (name "unconnected-(CN7-PD1{slash}PH1{slash}PF1-Pad31)") (class "Default")
      (node (ref "CN7") (pin "31") (pinfunction "PD1/PH1/PF1_31") (pintype "passive"))
    )
    (net (code "67") (name "unconnected-(CN7-PD2-Pad4)") (class "Default")
      (node (ref "CN7") (pin "4") (pinfunction "PD2_4") (pintype "passive"))
    )
    (net (code "68") (name "unconnected-(CN7-Pad10)") (class "Default")
      (node (ref "CN7") (pin "10") (pintype "passive"))
    )
    (net (code "69") (name "unconnected-(CN7-Pad26)") (class "Default")
      (node (ref "CN7") (pin "26") (pintype "passive"))
    )
    (net (code "70") (name "unconnected-(CN7-VBAT-Pad33)") (class "Default")
      (node (ref "CN7") (pin "33") (pinfunction "VBAT_33") (pintype "passive"))
    )
    (net (code "71") (name "unconnected-(CN7-VIN-Pad24)") (class "Default")
      (node (ref "CN7") (pin "24") (pinfunction "VIN_24") (pintype "passive"))
    )
    (net (code "72") (name "unconnected-(CN10-+3V3-Pad16)") (class "Default")
      (node (ref "CN10") (pin "16") (pinfunction "+3V3_16") (pintype "passive"))
    )
    (net (code "73") (name "unconnected-(CN10-+5V-Pad18)") (class "Default")
      (node (ref "CN10") (pin "18") (pinfunction "+5V_18") (pintype "passive"))
    )
    (net (code "74") (name "unconnected-(CN10-BOOT0-Pad7)") (class "Default")
      (node (ref "CN10") (pin "7") (pinfunction "BOOT0_7") (pintype "passive"))
    )
    (net (code "75") (name "unconnected-(CN10-E5V-Pad6)") (class "Default")
      (node (ref "CN10") (pin "6") (pinfunction "E5V_6") (pintype "passive"))
    )
    (net (code "76") (name "unconnected-(CN10-GND-Pad8)") (class "Default")
      (node (ref "CN10") (pin "8") (pinfunction "GND_8") (pintype "passive"))
    )
    (net (code "77") (name "unconnected-(CN10-GND-Pad19)") (class "Default")
      (node (ref "CN10") (pin "19") (pinfunction "GND_19") (pintype "passive"))
    )
    (net (code "78") (name "unconnected-(CN10-GND-Pad22)") (class "Default")
      (node (ref "CN10") (pin "22") (pinfunction "GND_22") (pintype "passive"))
    )
    (net (code "79") (name "unconnected-(CN10-PA0-Pad28)") (class "Default")
      (node (ref "CN10") (pin "28") (pinfunction "PA0_28") (pintype "passive"))
    )
    (net (code "80") (name "unconnected-(CN10-PA1-Pad30)") (class "Default")
      (node (ref "CN10") (pin "30") (pinfunction "PA1_30") (pintype "passive"))
    )
    (net (code "81") (name "unconnected-(CN10-PB0-Pad34)") (class "Default")
      (node (ref "CN10") (pin "34") (pinfunction "PB0_34") (pintype "passive"))
    )
    (net (code "82") (name "unconnected-(CN10-PC0{slash}PB9-Pad38)") (class "Default")
      (node (ref "CN10") (pin "38") (pinfunction "PC0/PB9_38") (pintype "passive"))
    )
    (net (code "83") (name "unconnected-(CN10-PC1{slash}PB8-Pad36)") (class "Default")
      (node (ref "CN10") (pin "36") (pinfunction "PC1/PB8_36") (pintype "passive"))
    )
    (net (code "84") (name "unconnected-(CN10-PC2-Pad35)") (class "Default")
      (node (ref "CN10") (pin "35") (pinfunction "PC2_35") (pintype "passive"))
    )
    (net (code "85") (name "unconnected-(CN10-PC3-Pad37)") (class "Default")
      (node (ref "CN10") (pin "37") (pinfunction "PC3_37") (pintype "passive"))
    )
    (net (code "86") (name "unconnected-(CN10-PC10-Pad1)") (class "Default")
      (node (ref "CN10") (pin "1") (pinfunction "PC10_1") (pintype "passive"))
    )
    (net (code "87") (name "unconnected-(CN10-PC11-Pad2)") (class "Default")
      (node (ref "CN10") (pin "2") (pinfunction "PC11_2") (pintype "passive"))
    )
    (net (code "88") (name "unconnected-(CN10-PC14-Pad25)") (class "Default")
      (node (ref "CN10") (pin "25") (pinfunction "PC14_25") (pintype "passive"))
    )
    (net (code "89") (name "unconnected-(CN10-PD1{slash}PH1{slash}PF1-Pad31)") (class "Default")
      (node (ref "CN10") (pin "31") (pinfunction "PD1/PH1/PF1_31") (pintype "passive"))
    )
    (net (code "90") (name "unconnected-(CN10-PD2-Pad4)") (class "Default")
      (node (ref "CN10") (pin "4") (pinfunction "PD2_4") (pintype "passive"))
    )
    (net (code "91") (name "unconnected-(CN10-Pad10)") (class "Default")
      (node (ref "CN10") (pin "10") (pintype "passive"))
    )
    (net (code "92") (name "unconnected-(J601-Pad2)") (class "Default")
      (node (ref "J601") (pin "2") (pinfunction "2_2") (pintype "passive"))
    )
    (net (code "93") (name "unconnected-(J602-Pad2)") (class "Default")
      (node (ref "J602") (pin "2") (pinfunction "2_2") (pintype "passive"))
    )
    (net (code "94") (name "unconnected-(J701-Pad2)") (class "Default")
      (node (ref "J701") (pin "2") (pinfunction "2_2") (pintype "passive"))
    )
    (net (code "95") (name "unconnected-(J702-Pad2)") (class "Default")
      (node (ref "J702") (pin "2") (pinfunction "2_2") (pintype "passive"))
    )
    (net (code "96") (name "unconnected-(J800-Pad2)") (class "Default")
      (node (ref "J800") (pin "2") (pinfunction "2_2") (pintype "passive"))
    )
    (net (code "97") (name "unconnected-(J900-Pad2)") (class "Default")
      (node (ref "J900") (pin "2") (pinfunction "2_2") (pintype "passive"))
    )
    (net (code "98") (name "unconnected-(U100-VREF-Pad5)") (class "Default")
      (node (ref "U100") (pin "5") (pinfunction "VREF_5") (pintype "output"))
    )
    (net (code "99") (name "unconnected-(XM600-Monitor_n-Pad18)") (class "Default")
      (node (ref "XM600") (pin "18") (pinfunction "Monitor_n_18") (pintype "output"))
    )
    (net (code "100") (name "unconnected-(XM600-Ready-Pad19)") (class "Default")
      (node (ref "XM600") (pin "19") (pinfunction "Ready_19") (pintype "output"))
    )
    (net (code "101") (name "unconnected-(XM600-Set_current_limit-Pad25)") (class "Default")
      (node (ref "XM600") (pin "25") (pinfunction "Set_current_limit_25") (pintype "passive"))
    )
    (net (code "102") (name "unconnected-(XM600-nc-Pad12)") (class "Default")
      (node (ref "XM600") (pin "12") (pinfunction "nc_12") (pintype "passive"))
    )
    (net (code "103") (name "unconnected-(XM700-Monitor_n-Pad18)") (class "Default")
      (node (ref "XM700") (pin "18") (pinfunction "Monitor_n_18") (pintype "output"))
    )
    (net (code "104") (name "unconnected-(XM700-Ready-Pad19)") (class "Default")
      (node (ref "XM700") (pin "19") (pinfunction "Ready_19") (pintype "output"))
    )
    (net (code "105") (name "unconnected-(XM700-Set_current_limit-Pad25)") (class "Default")
      (node (ref "XM700") (pin "25") (pinfunction "Set_current_limit_25") (pintype "passive"))
    )
    (net (code "106") (name "unconnected-(XM700-nc-Pad12)") (class "Default")
      (node (ref "XM700") (pin "12") (pinfunction "nc_12") (pintype "passive"))
    )
  )
)
